# PM3510-AS5147P.net
KiCad netlist of a schematic drawn in EasyEDA Pro
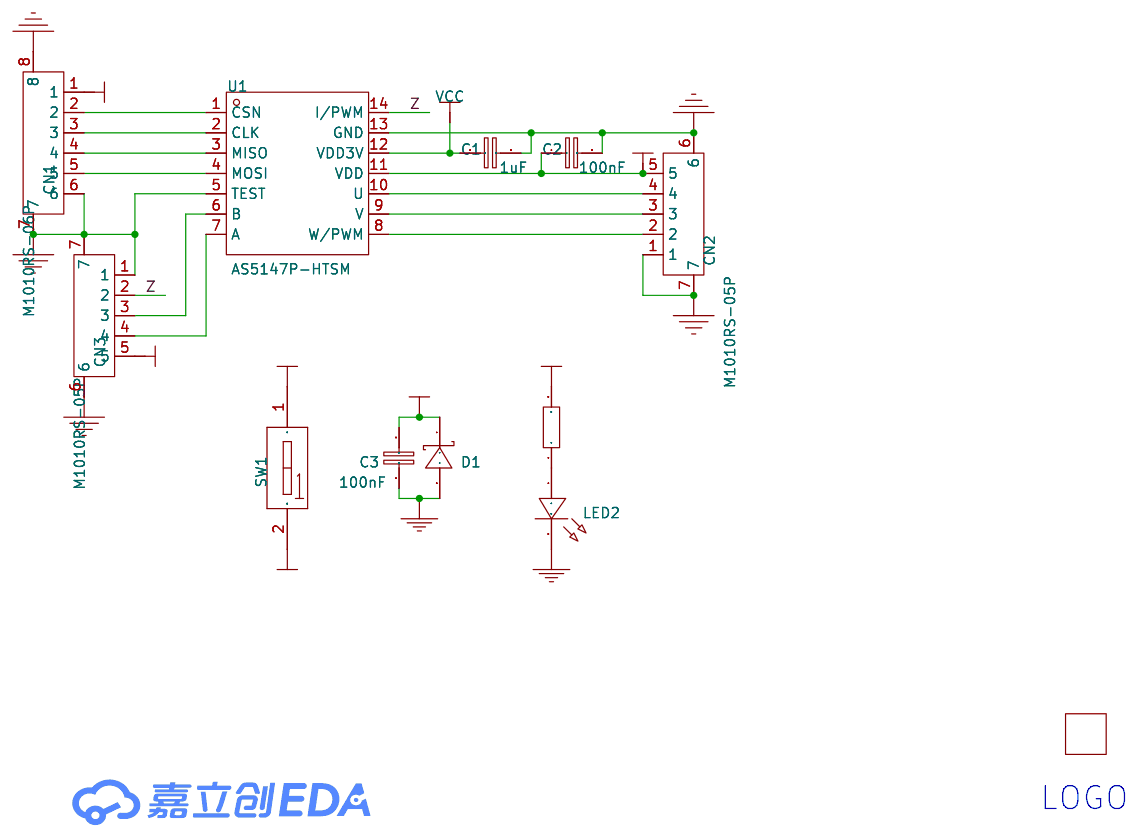
[diagram p0: schematic sheet]

(export (version "E")
  (design (tool "Eeschema 10.0.6"))
  (components
    (comp (ref "C1")
      (value "1uF")
      (fields
        (field (name "Manufacturer Part") "CL10A105KB8NNNC")
        (field (name "Manufacturer") "SAMSUNG(三星)")
      )
      (libsource (lib "easyedapro") (part "C0603"))
    )
    (comp (ref "C2")
      (value "100nF")
      (fields
        (field (name "Manufacturer Part") "CC0603KRX7R9BB104")
        (field (name "Manufacturer") "YAGEO(国巨)")
      )
      (libsource (lib "easyedapro") (part "C0603"))
    )
    (comp (ref "C3")
      (value "100nF")
      (fields
        (field (name "Manufacturer Part") "CC0603KRX7R9BB104")
        (field (name "Manufacturer") "YAGEO(国巨)")
      )
      (libsource (lib "easyedapro") (part "C0603"))
    )
    (comp (ref "CN1")
      (value "M1010RS-06P")
      (footprint "easyedapro:CONN-SMD_M1010RS-06P")
      (description "插针结构:1x6P;间距:1mm;安装方式:卧贴;参考系列:-;总PIN数:6P;排数:1;每排PIN数:6;行距:-;额定电流:1A;工作温度范围:-25°C~+85°C;")
      (fields (field (name "Manufacturer") "XFCN(兴飞)"))
      (libsource (lib "easyedapro") (part "M1010RS-06P"))
    )
    (comp (ref "CN2")
      (value "M1010RS-05P")
      (footprint "easyedapro:CONN-SMD_M1010RS-05P")
      (description "插针结构:1x5P;间距:1mm;安装方式:卧贴;参考系列:-;总PIN数:5P;排数:1;每排PIN数:5;行距:-;额定电流:1A;工作温度范围:-25°C~+85°C;")
      (fields (field (name "Manufacturer") "XFCN(兴飞)"))
      (libsource (lib "easyedapro") (part "M1010RS-05P"))
    )
    (comp (ref "CN3")
      (value "M1010RS-05P")
      (footprint "easyedapro:CONN-SMD_M1010RS-05P")
      (description "插针结构:1x5P;间距:1mm;安装方式:卧贴;参考系列:-;总PIN数:5P;排数:1;每排PIN数:5;行距:-;额定电流:1A;工作温度范围:-25°C~+85°C;")
      (fields (field (name "Manufacturer") "XFCN(兴飞)"))
      (libsource (lib "easyedapro") (part "M1010RS-05P"))
    )
    (comp (ref "D1") (value "SMFJ5.0A") (libsource (lib "easyedapro") (part "SMFJ5.0A")))
    (comp (ref "H1")
      (value "MoonGrt")
      (footprint "easyedapro:MoonGrt")
      (libsource (lib "easyedapro") (part "MoonGrt"))
    )
    (comp (ref "LED2")
      (value "~")
      (footprint "easyedapro:LED0603")
      (libsource (lib "easyedapro") (part "LED0603B"))
    )
    (comp (ref "R2")
      (value "1kΩ")
      (footprint "easyedapro:R0603")
      (libsource (lib "easyedapro") (part "R0603"))
    )
    (comp (ref "SW1") (value "DSHP01TSGET") (libsource (lib "easyedapro") (part "DSHP01TSGET")))
    (comp (ref "U1")
      (value "AS5147P-HTSM")
      (footprint "easyedapro:TSSOP-14_L5.0-W4.4-P0.65-LS6.5-BL")
      (fields (field (name "Manufacturer") "AMS"))
      (libsource (lib "easyedapro") (part "AS5147P-HTSM"))
    )
  )
  (nets
    (net (code "1") (name "/Z") (class "Default")
      (node (ref "CN3") (pin "2") (pinfunction "2_2") (pintype "unspecified"))
      (node (ref "U1") (pin "14") (pinfunction "I/PWM_14") (pintype "unspecified"))
    )
    (net (code "2") (name "5V") (class "Default")
      (node (ref "C2") (pin "1") (pinfunction "1_1") (pintype "unspecified"))
      (node (ref "CN1") (pin "1") (pinfunction "1_1") (pintype "unspecified"))
      (node (ref "CN2") (pin "5") (pinfunction "5_5") (pintype "unspecified"))
      (node (ref "CN3") (pin "5") (pinfunction "5_5") (pintype "unspecified"))
      (node (ref "SW1") (pin "2") (pinfunction "B1_2") (pintype "input"))
      (node (ref "U1") (pin "11") (pinfunction "VDD_11") (pintype "unspecified"))
    )
    (net (code "3") (name "GND") (class "Default")
      (node (ref "C1") (pin "2") (pinfunction "2_2") (pintype "unspecified"))
      (node (ref "C2") (pin "2") (pinfunction "2_2") (pintype "unspecified"))
      (node (ref "C3") (pin "1") (pinfunction "1_1") (pintype "unspecified"))
      (node (ref "CN1") (pin "6") (pinfunction "6_6") (pintype "unspecified"))
      (node (ref "CN1") (pin "7") (pinfunction "7_7") (pintype "unspecified"))
      (node (ref "CN1") (pin "8") (pinfunction "8_8") (pintype "unspecified"))
      (node (ref "CN2") (pin "1") (pinfunction "1_1") (pintype "unspecified"))
      (node (ref "CN2") (pin "6") (pinfunction "6_6") (pintype "unspecified"))
      (node (ref "CN2") (pin "7") (pinfunction "7_7") (pintype "unspecified"))
      (node (ref "CN3") (pin "1") (pinfunction "1_1") (pintype "unspecified"))
      (node (ref "CN3") (pin "6") (pinfunction "6_6") (pintype "unspecified"))
      (node (ref "CN3") (pin "7") (pinfunction "7_7") (pintype "unspecified"))
      (node (ref "D1") (pin "2") (pinfunction "A_2") (pintype "unspecified"))
      (node (ref "LED2") (pin "2") (pinfunction "2_2") (pintype "unspecified"))
      (node (ref "U1") (pin "13") (pinfunction "GND_13") (pintype "unspecified"))
      (node (ref "U1") (pin "5") (pinfunction "TEST_5") (pintype "unspecified"))
    )
    (net (code "4") (name "Net-(LED2-Pad1)") (class "Default")
      (node (ref "LED2") (pin "1") (pinfunction "1_1") (pintype "unspecified"))
      (node (ref "R2") (pin "1") (pinfunction "1_1") (pintype "unspecified"))
    )
    (net (code "5") (name "Net-(U1-A)") (class "Default")
      (node (ref "CN3") (pin "4") (pinfunction "4_4") (pintype "unspecified"))
      (node (ref "U1") (pin "7") (pinfunction "A_7") (pintype "unspecified"))
    )
    (net (code "6") (name "Net-(U1-B)") (class "Default")
      (node (ref "CN3") (pin "3") (pinfunction "3_3") (pintype "unspecified"))
      (node (ref "U1") (pin "6") (pinfunction "B_6") (pintype "unspecified"))
    )
    (net (code "7") (name "Net-(U1-CLK)") (class "Default")
      (node (ref "CN1") (pin "3") (pinfunction "3_3") (pintype "unspecified"))
      (node (ref "U1") (pin "2") (pinfunction "CLK_2") (pintype "unspecified"))
    )
    (net (code "8") (name "Net-(U1-CSN)") (class "Default")
      (node (ref "CN1") (pin "2") (pinfunction "2_2") (pintype "unspecified"))
      (node (ref "U1") (pin "1") (pinfunction "CSN_1") (pintype "unspecified"))
    )
    (net (code "9") (name "Net-(U1-MISO)") (class "Default")
      (node (ref "CN1") (pin "4") (pinfunction "4_4") (pintype "unspecified"))
      (node (ref "U1") (pin "3") (pinfunction "MISO_3") (pintype "unspecified"))
    )
    (net (code "10") (name "Net-(U1-MOSI)") (class "Default")
      (node (ref "CN1") (pin "5") (pinfunction "5_5") (pintype "unspecified"))
      (node (ref "U1") (pin "4") (pinfunction "MOSI_4") (pintype "unspecified"))
    )
    (net (code "11") (name "Net-(U1-U)") (class "Default")
      (node (ref "CN2") (pin "4") (pinfunction "4_4") (pintype "unspecified"))
      (node (ref "U1") (pin "10") (pinfunction "U_10") (pintype "unspecified"))
    )
    (net (code "12") (name "Net-(U1-V)") (class "Default")
      (node (ref "CN2") (pin "3") (pinfunction "3_3") (pintype "unspecified"))
      (node (ref "U1") (pin "9") (pinfunction "V_9") (pintype "unspecified"))
    )
    (net (code "13") (name "Net-(U1-W{slash}PWM)") (class "Default")
      (node (ref "CN2") (pin "2") (pinfunction "2_2") (pintype "unspecified"))
      (node (ref "U1") (pin "8") (pinfunction "W/PWM_8") (pintype "unspecified"))
    )
    (net (code "14") (name "VCC") (class "Default")
      (node (ref "C1") (pin "1") (pinfunction "1_1") (pintype "unspecified"))
      (node (ref "C3") (pin "2") (pinfunction "2_2") (pintype "unspecified"))
      (node (ref "D1") (pin "1") (pinfunction "K_1") (pintype "unspecified"))
      (node (ref "R2") (pin "2") (pinfunction "2_2") (pintype "unspecified"))
      (node (ref "SW1") (pin "1") (pinfunction "A1_1") (pintype "input"))
      (node (ref "U1") (pin "12") (pinfunction "VDD3V_12") (pintype "unspecified"))
    )
  )
)
